# witch-phase2a.net
KiCad netlist of a schematic drawn in EAGLE
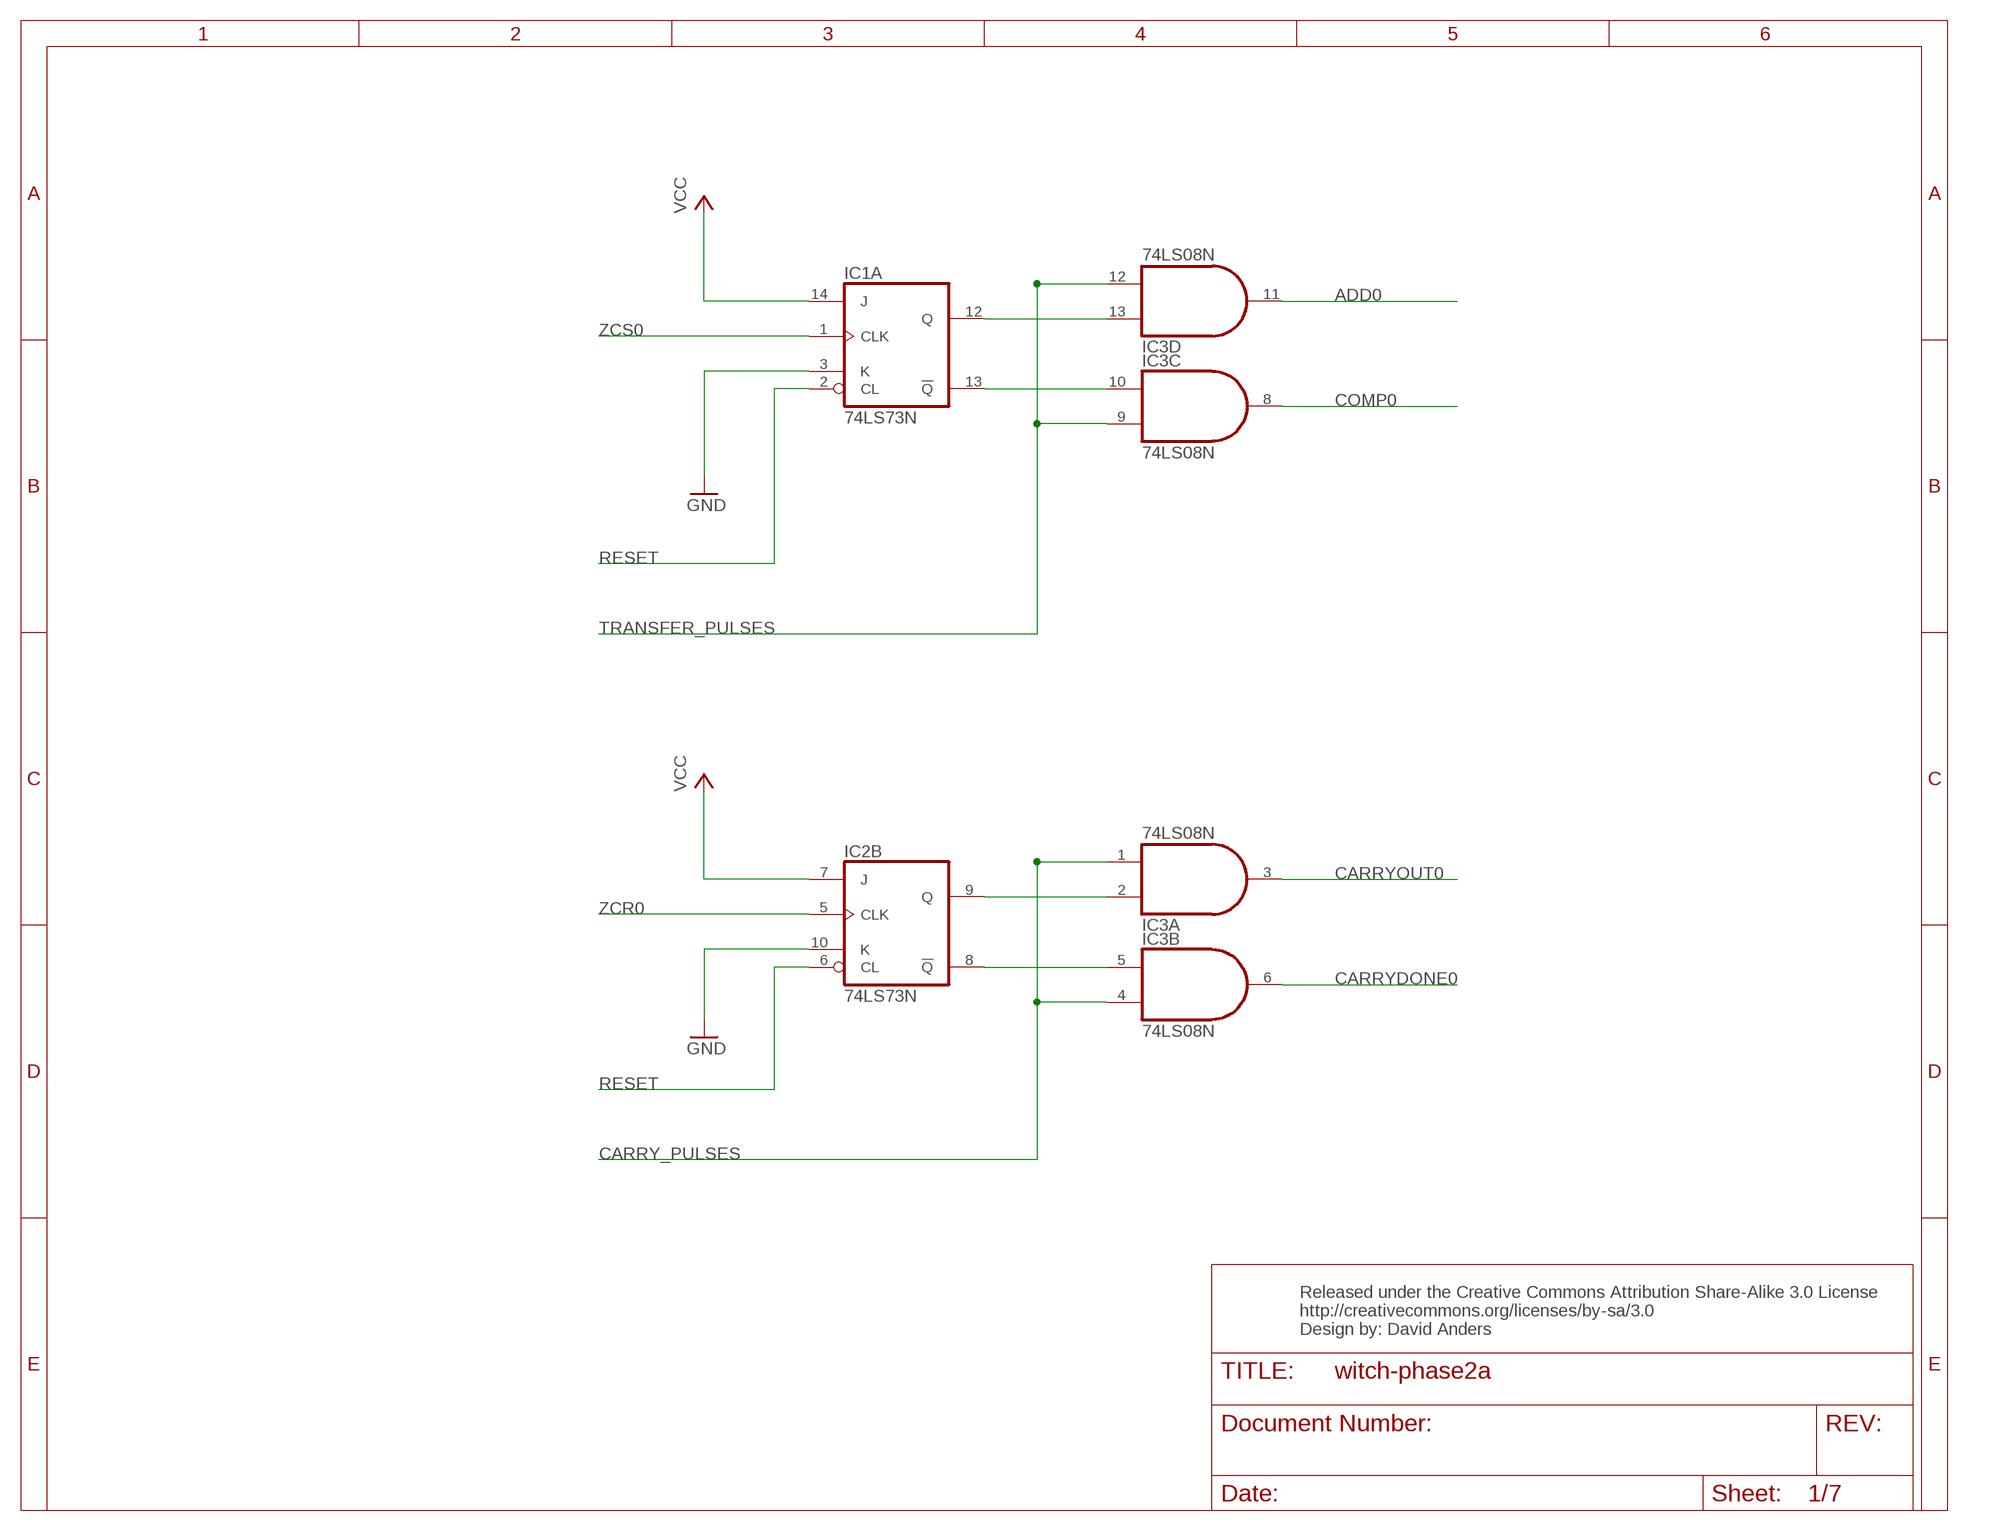
[diagram p0: schematic, sheet 1]
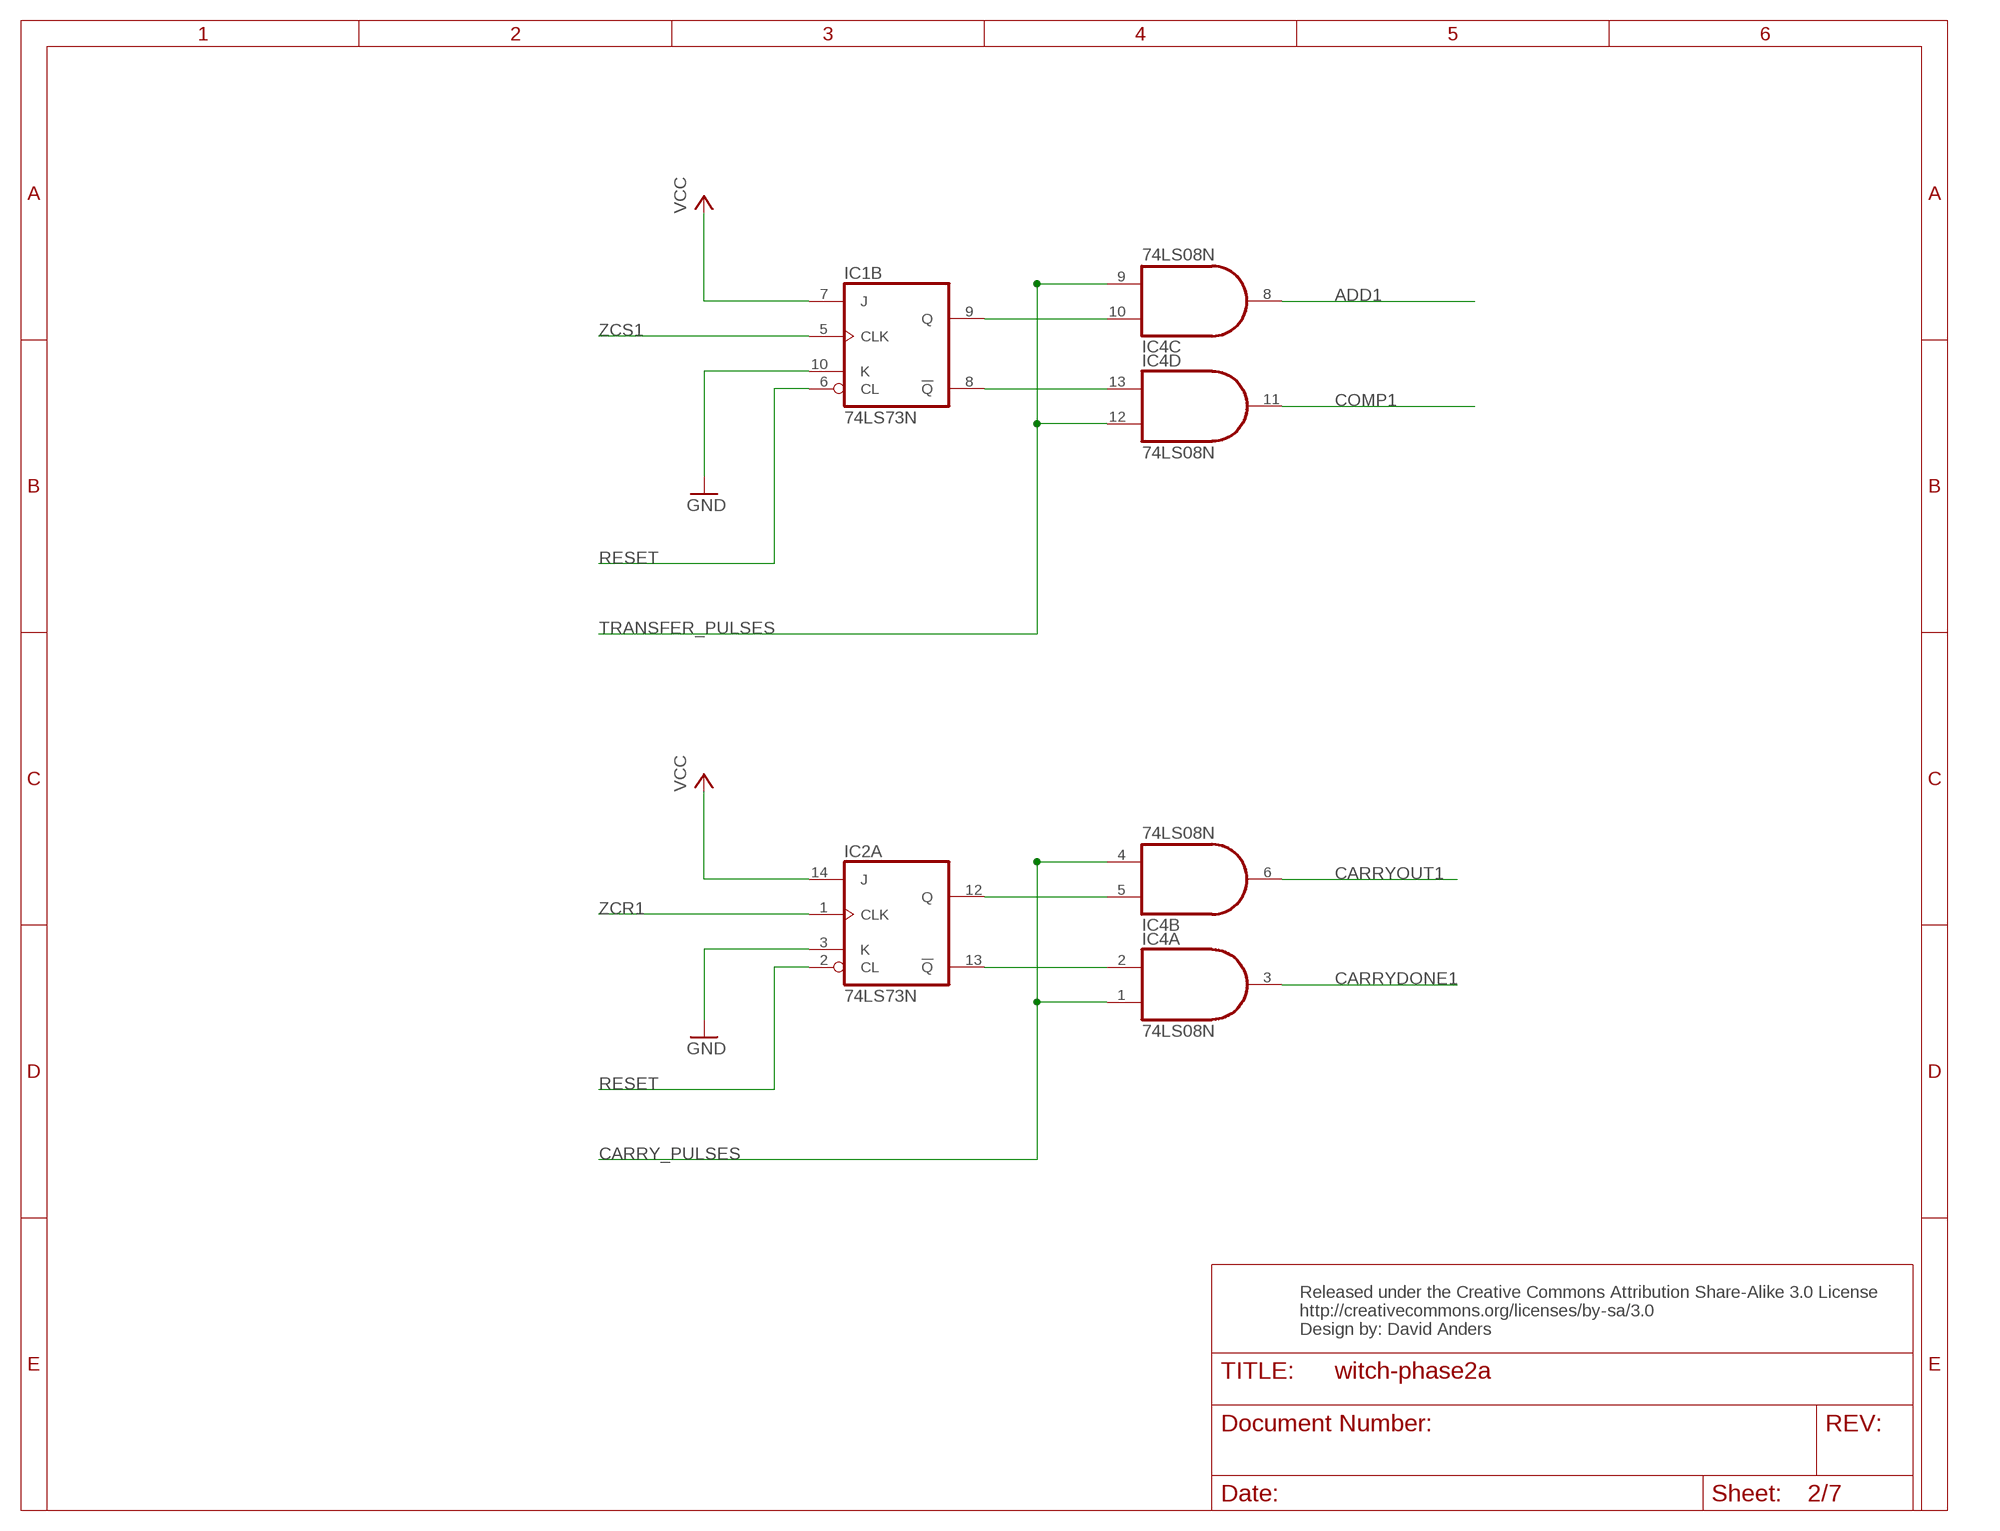
[diagram p1: schematic, sheet 2]
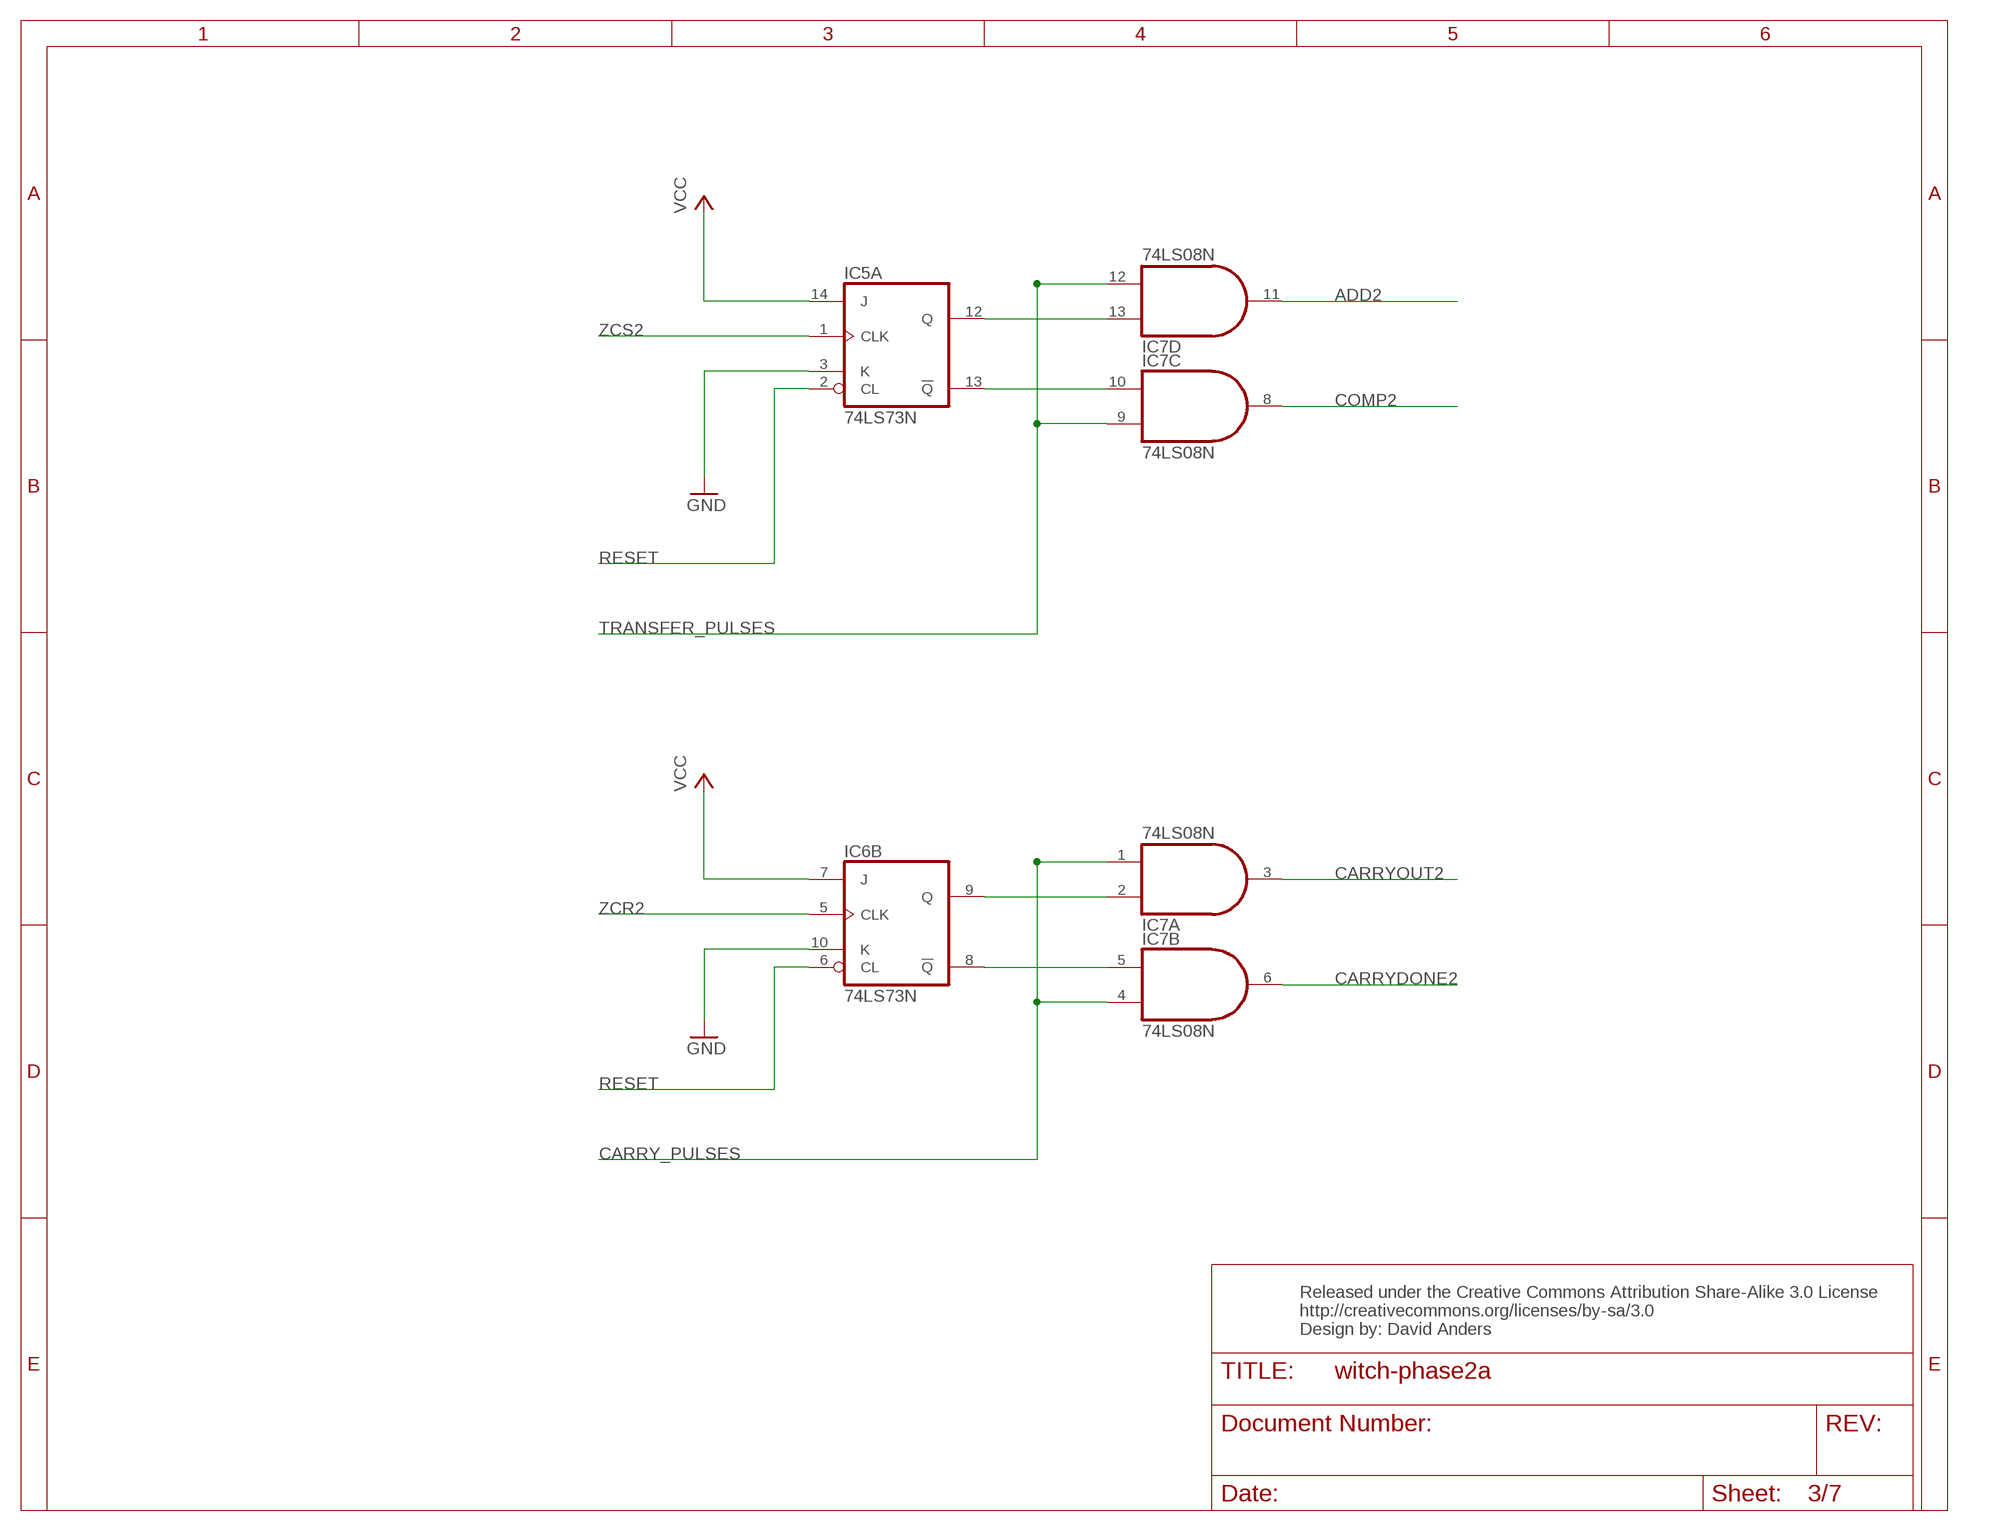
[diagram p2: schematic, sheet 3]
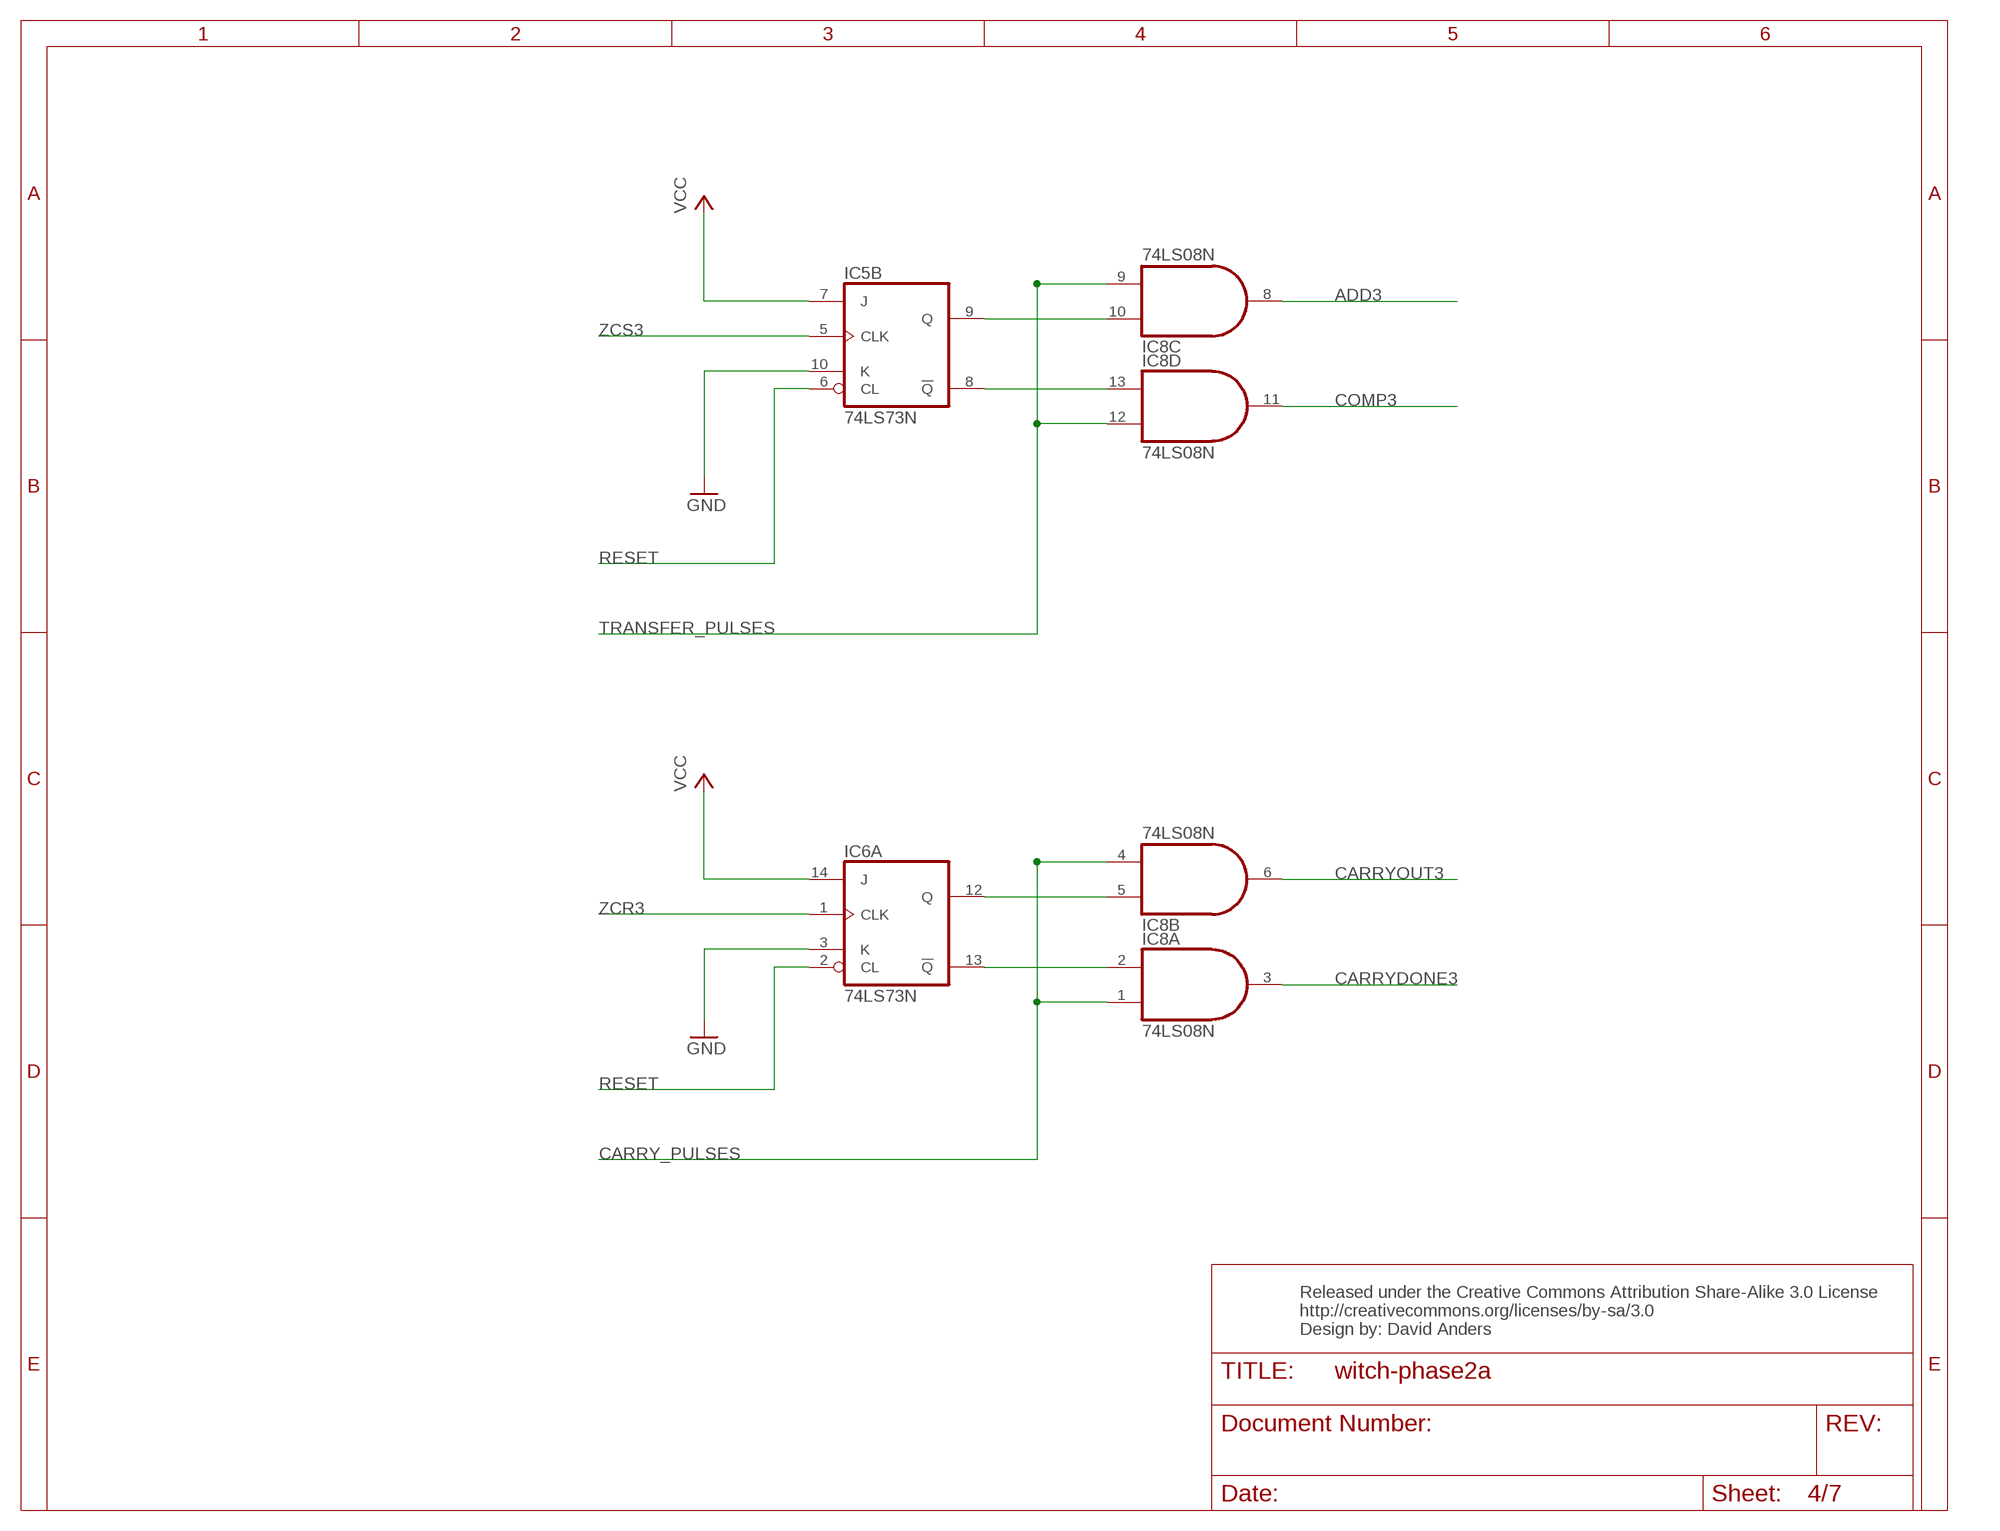
[diagram p3: schematic, sheet 4]
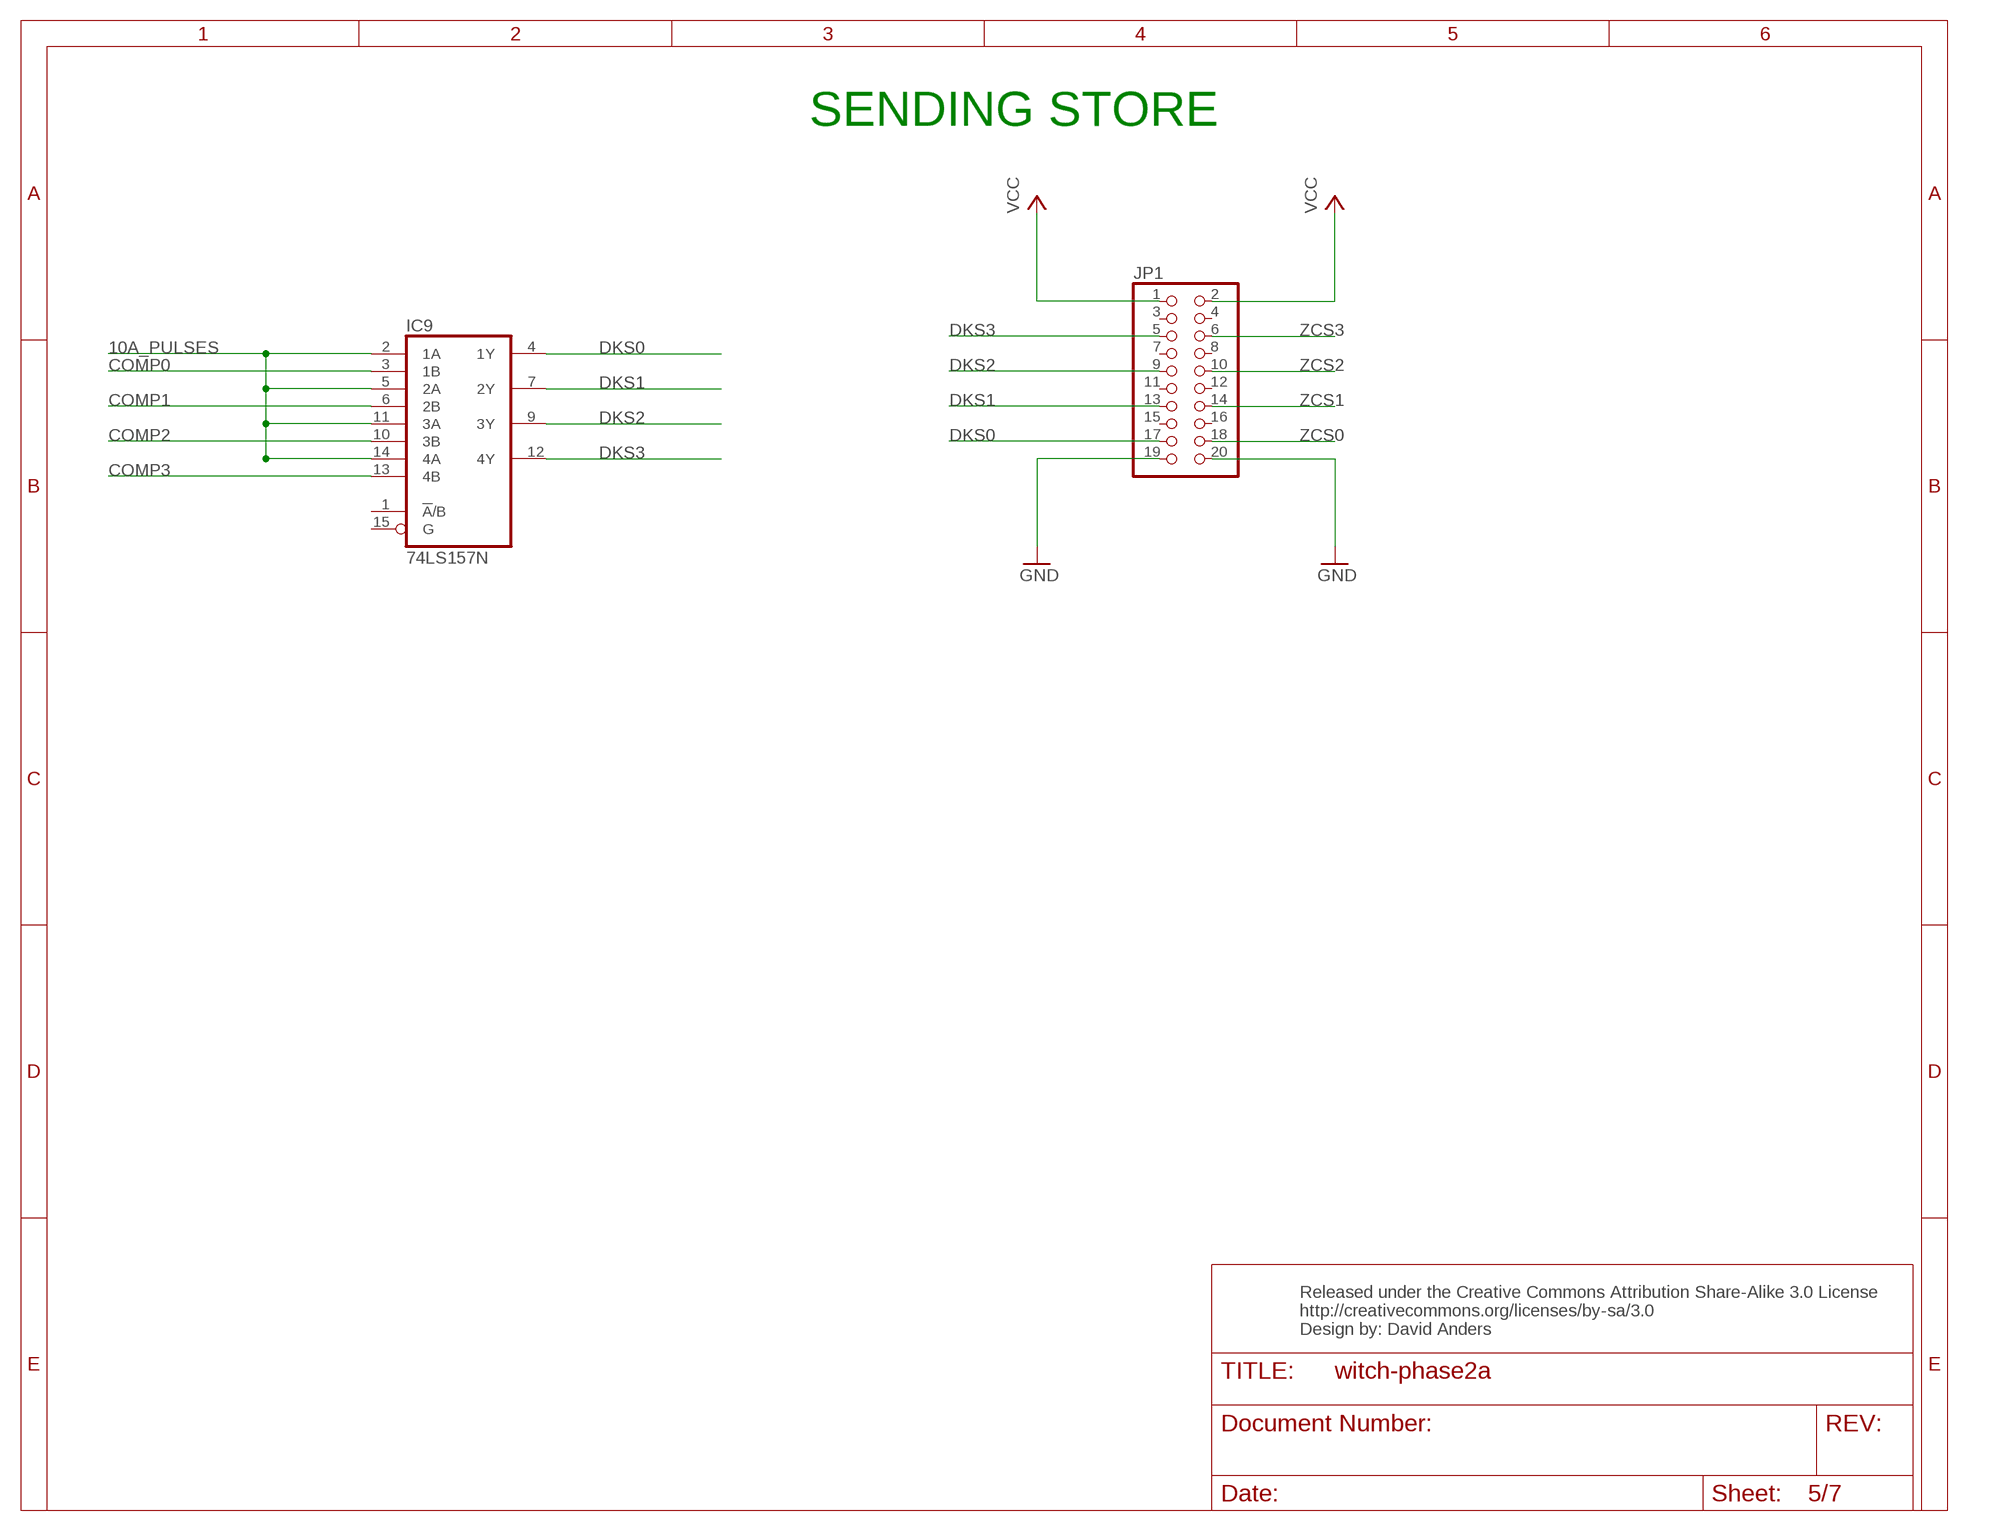
[diagram p4: schematic, sheet 5]
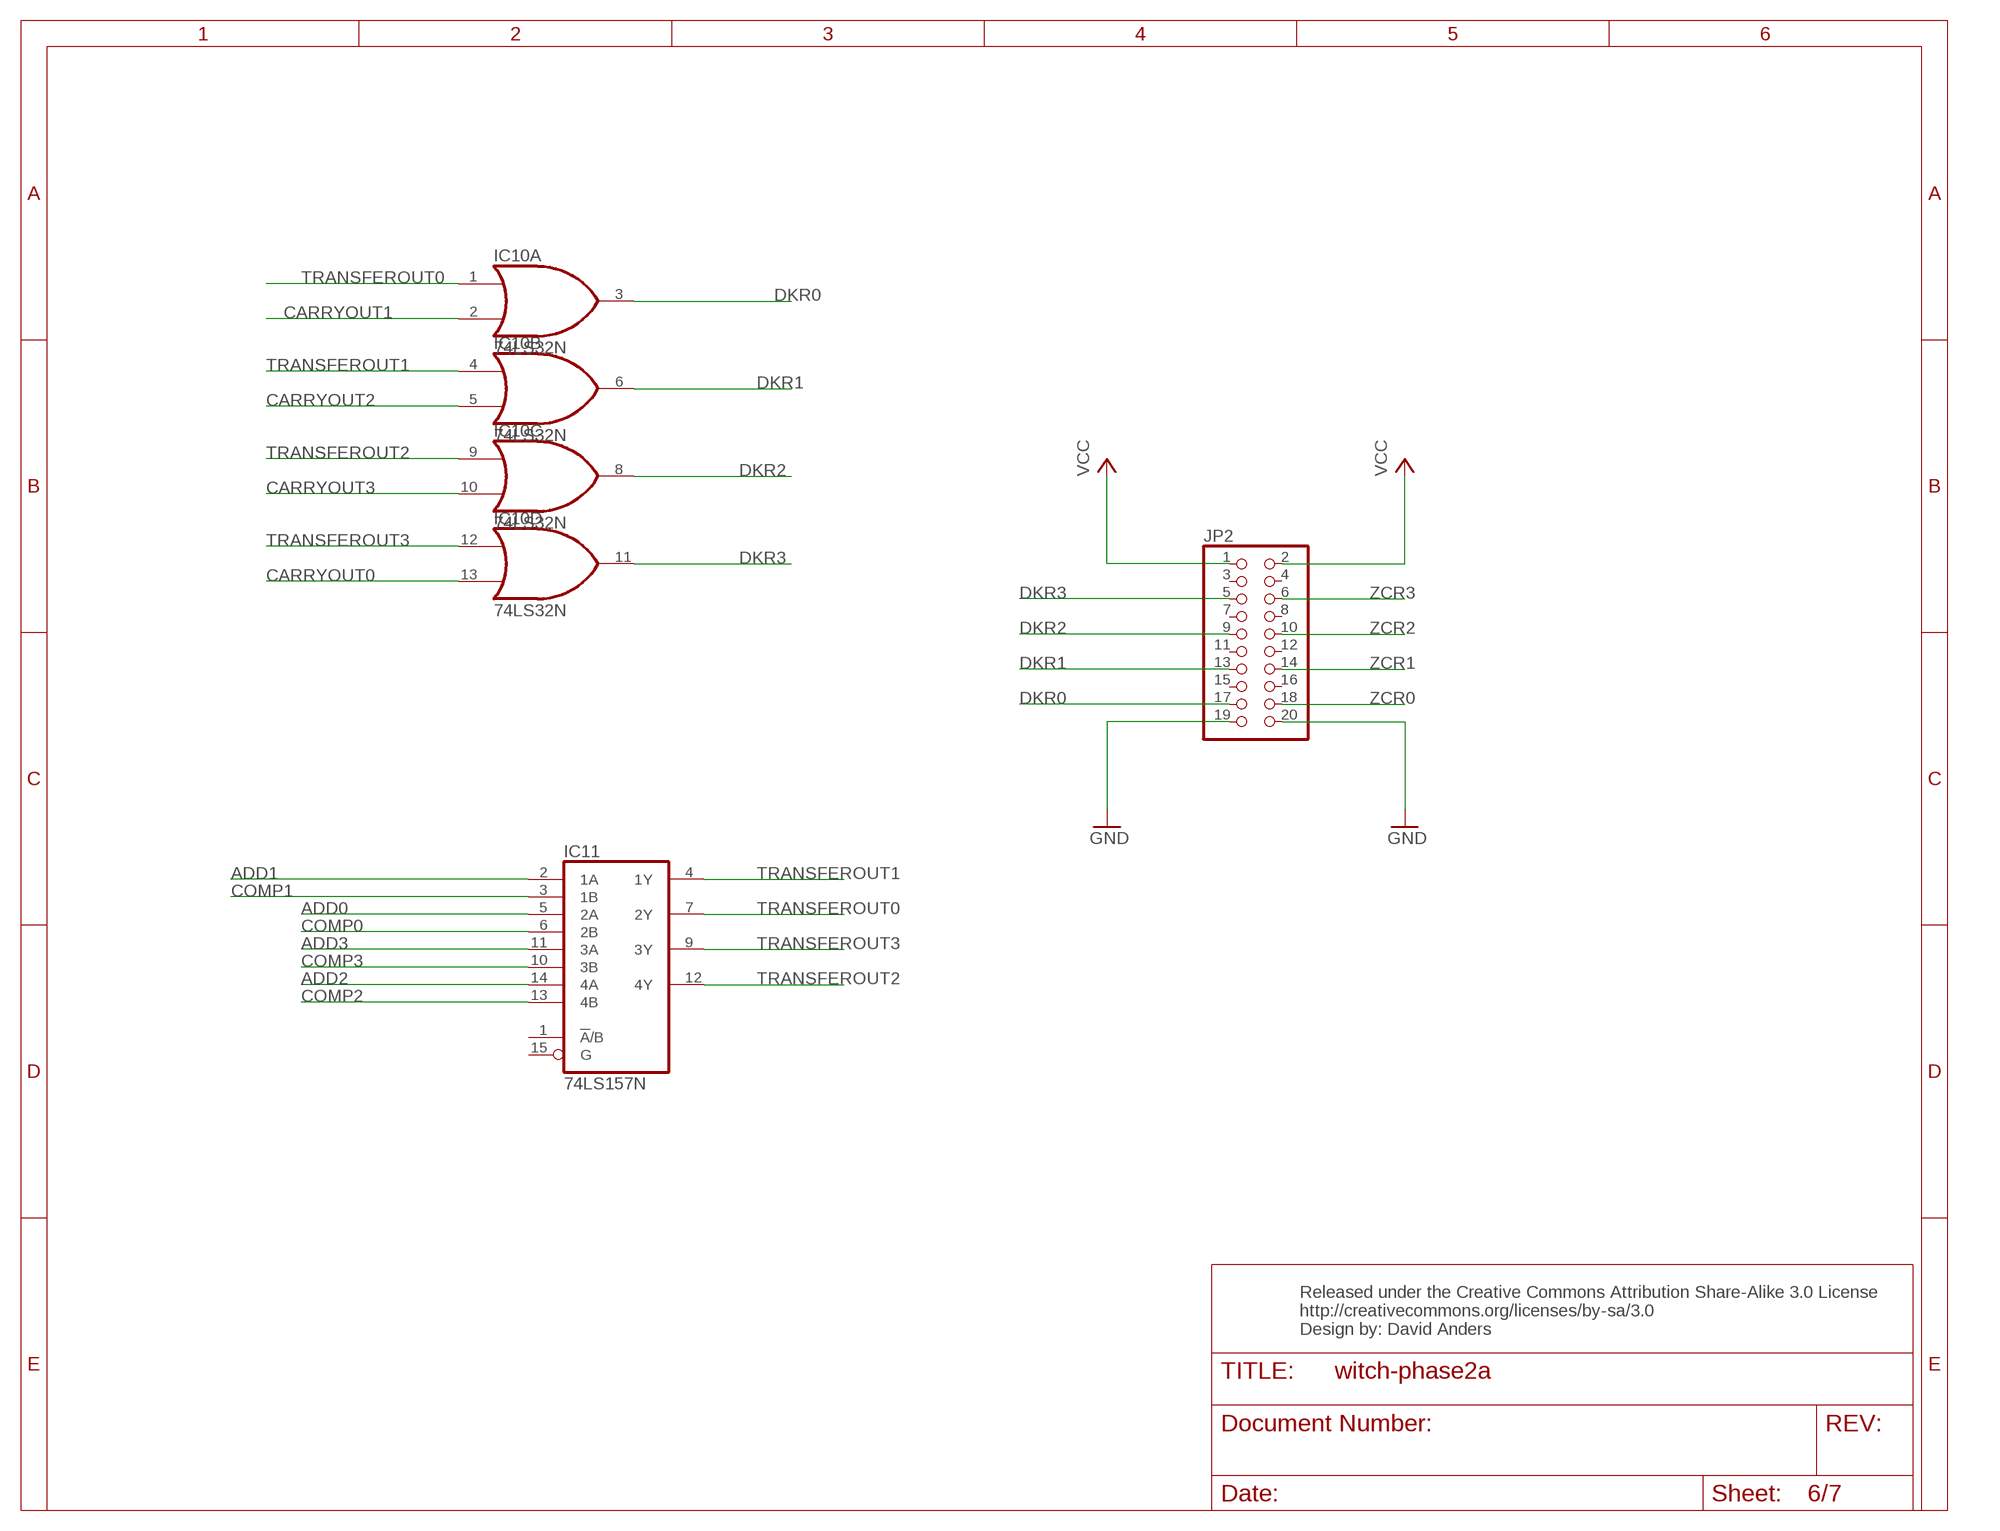
[diagram p5: schematic, sheet 6]
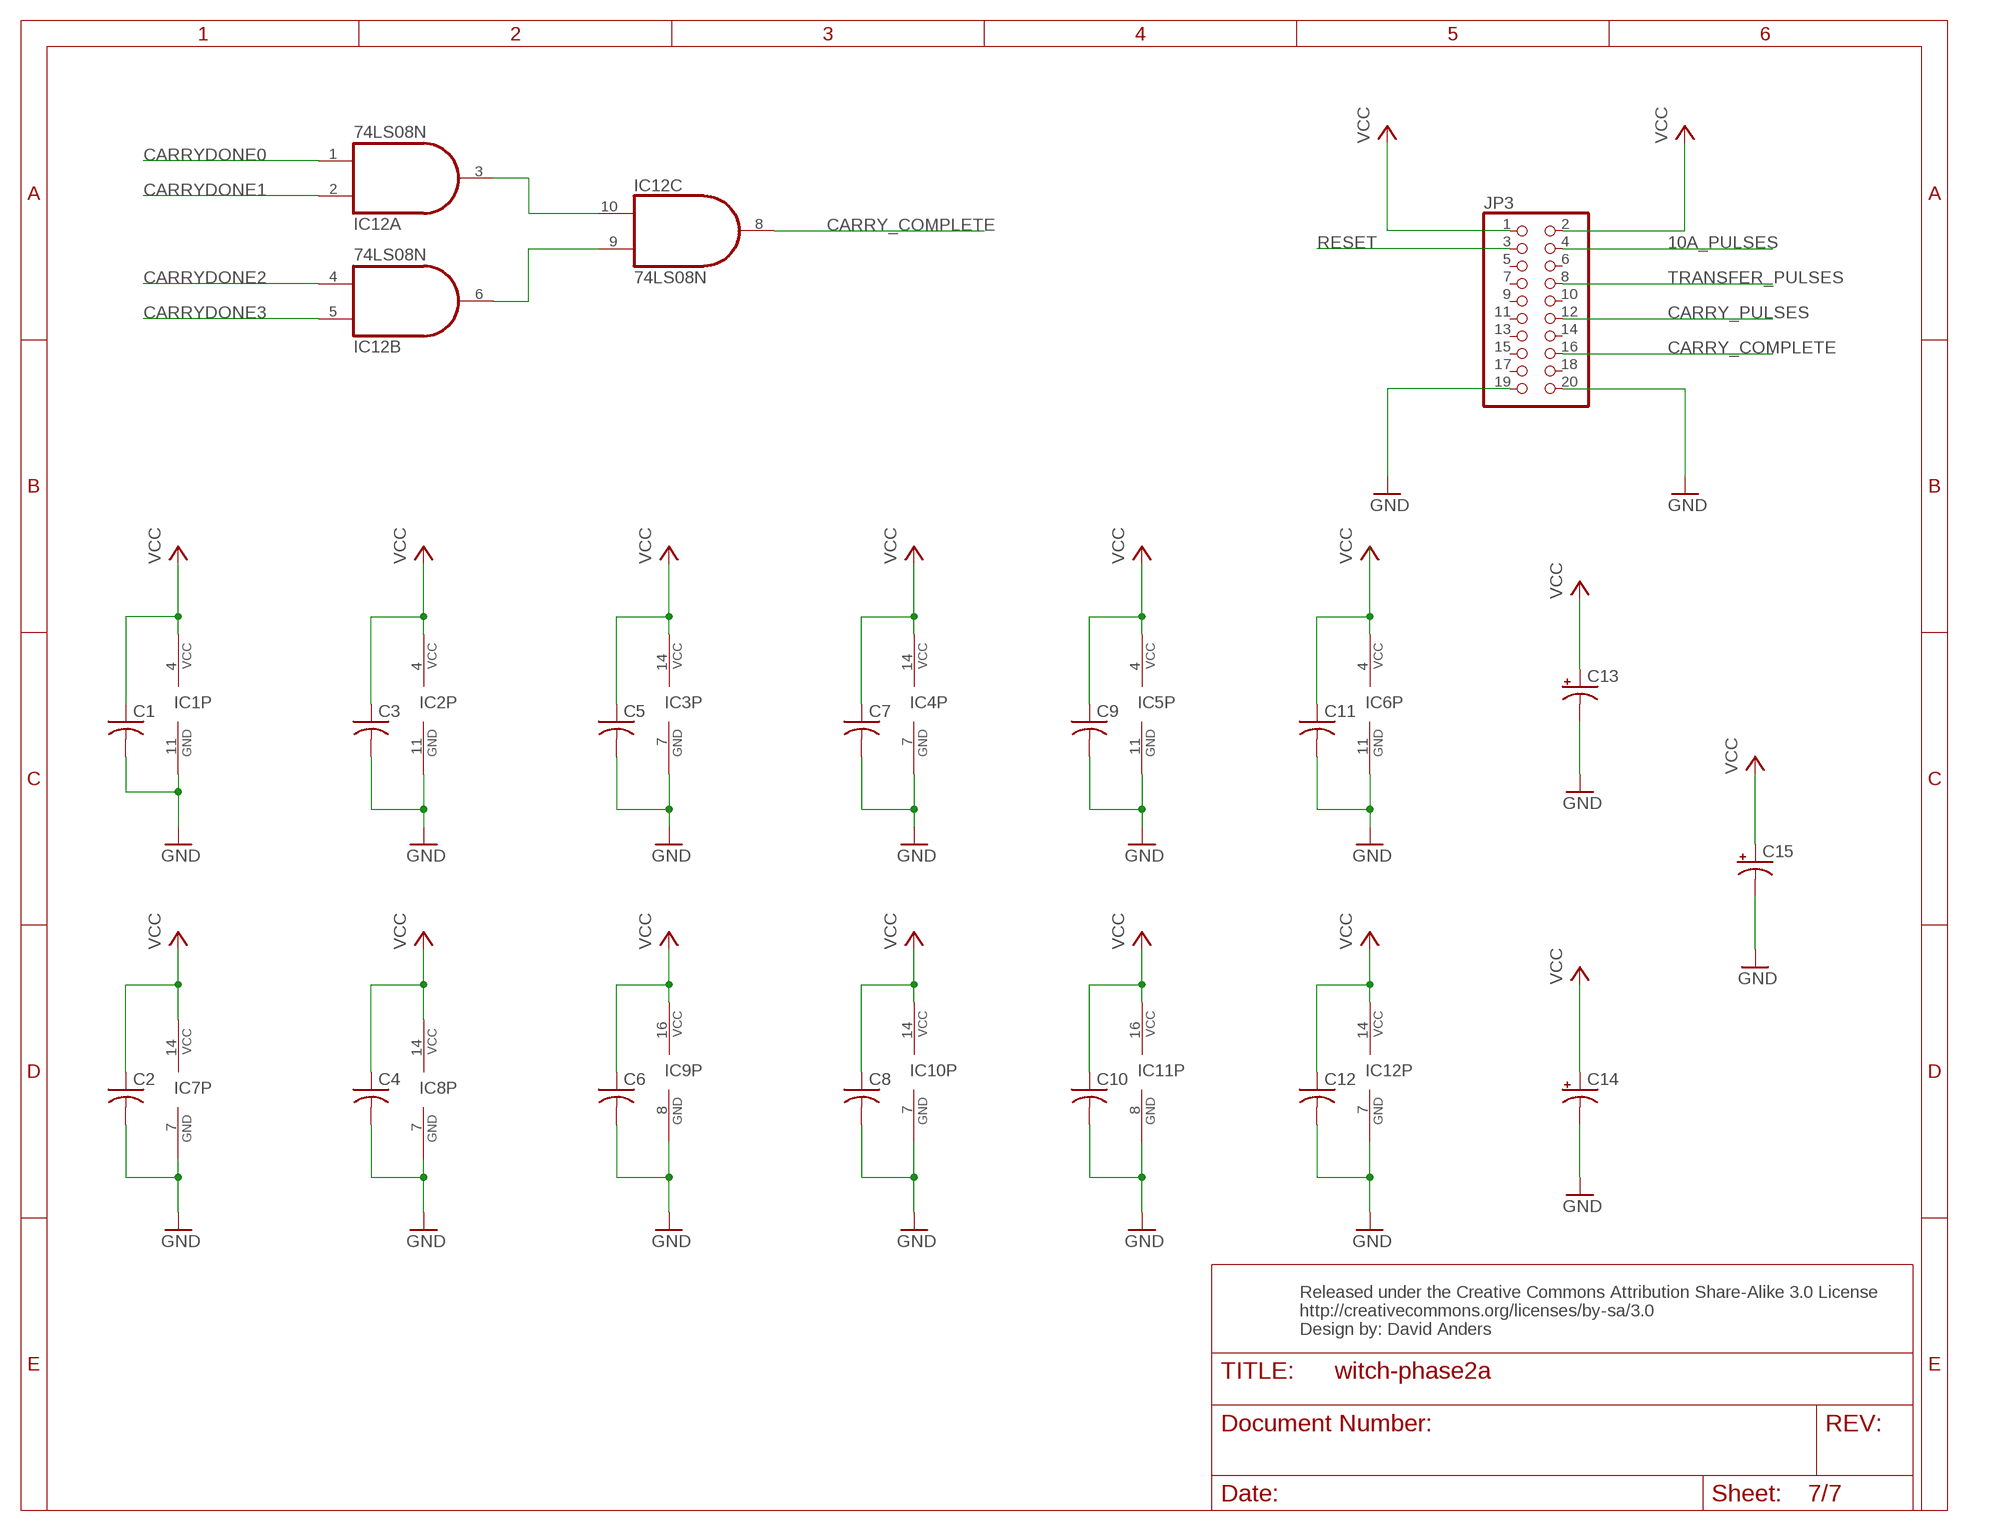
[diagram p6: schematic, sheet 7]

(export (version "E")
  (design (tool "Eeschema 10.0.6"))
  (components
    (comp (ref "IC9")
      (value "74LS157N")
      (footprint "eagle-import:DIL16")
      (libsource (lib "eagle-import") (part "74157NLS"))
    )
    (comp (ref "JP1")
      (value "PINHD-2X10")
      (footprint "eagle-import:2X10")
      (libsource (lib "eagle-import") (part "PINHD-2X10"))
    )
    (comp (ref "IC10")
      (value "74LS32N")
      (footprint "eagle-import:DIL14")
      (libsource (lib "eagle-import") (part "7432NLS"))
    )
    (comp (ref "IC11")
      (value "74LS157N")
      (footprint "eagle-import:DIL16")
      (libsource (lib "eagle-import") (part "74157NLS"))
    )
    (comp (ref "JP2")
      (value "PINHD-2X10")
      (footprint "eagle-import:2X10")
      (libsource (lib "eagle-import") (part "PINHD-2X10"))
    )
    (comp (ref "C1")
      (value "C-US025-025X050")
      (footprint "eagle-import:C025-025X050")
      (libsource (lib "eagle-import") (part "C-US025-025X050"))
    )
    (comp (ref "C2")
      (value "C-US025-025X050")
      (footprint "eagle-import:C025-025X050")
      (libsource (lib "eagle-import") (part "C-US025-025X050"))
    )
    (comp (ref "C3")
      (value "C-US025-025X050")
      (footprint "eagle-import:C025-025X050")
      (libsource (lib "eagle-import") (part "C-US025-025X050"))
    )
    (comp (ref "C4")
      (value "C-US025-025X050")
      (footprint "eagle-import:C025-025X050")
      (libsource (lib "eagle-import") (part "C-US025-025X050"))
    )
    (comp (ref "C5")
      (value "C-US025-025X050")
      (footprint "eagle-import:C025-025X050")
      (libsource (lib "eagle-import") (part "C-US025-025X050"))
    )
    (comp (ref "C6")
      (value "C-US025-025X050")
      (footprint "eagle-import:C025-025X050")
      (libsource (lib "eagle-import") (part "C-US025-025X050"))
    )
    (comp (ref "C7")
      (value "C-US025-025X050")
      (footprint "eagle-import:C025-025X050")
      (libsource (lib "eagle-import") (part "C-US025-025X050"))
    )
    (comp (ref "C8")
      (value "C-US025-025X050")
      (footprint "eagle-import:C025-025X050")
      (libsource (lib "eagle-import") (part "C-US025-025X050"))
    )
    (comp (ref "C9")
      (value "C-US025-025X050")
      (footprint "eagle-import:C025-025X050")
      (libsource (lib "eagle-import") (part "C-US025-025X050"))
    )
    (comp (ref "C10")
      (value "C-US025-025X050")
      (footprint "eagle-import:C025-025X050")
      (libsource (lib "eagle-import") (part "C-US025-025X050"))
    )
    (comp (ref "C11")
      (value "C-US025-025X050")
      (footprint "eagle-import:C025-025X050")
      (libsource (lib "eagle-import") (part "C-US025-025X050"))
    )
    (comp (ref "C12")
      (value "C-US025-025X050")
      (footprint "eagle-import:C025-025X050")
      (libsource (lib "eagle-import") (part "C-US025-025X050"))
    )
    (comp (ref "C13")
      (value "CPOL-USE2-5")
      (footprint "eagle-import:E2-5")
      (libsource (lib "eagle-import") (part "CPOL-USE2-5"))
    )
    (comp (ref "C14")
      (value "CPOL-USE2-5")
      (footprint "eagle-import:E2-5")
      (libsource (lib "eagle-import") (part "CPOL-USE2-5"))
    )
    (comp (ref "C15")
      (value "CPOL-USE2-5")
      (footprint "eagle-import:E2-5")
      (libsource (lib "eagle-import") (part "CPOL-USE2-5"))
    )
    (comp (ref "IC1")
      (value "74LS73N")
      (footprint "eagle-import:DIL14")
      (libsource (lib "eagle-import") (part "7473NLS"))
    )
    (comp (ref "IC2")
      (value "74LS73N")
      (footprint "eagle-import:DIL14")
      (libsource (lib "eagle-import") (part "7473NLS"))
    )
    (comp (ref "IC3")
      (value "74LS08N")
      (footprint "eagle-import:DIL14")
      (libsource (lib "eagle-import") (part "7408NLS"))
    )
    (comp (ref "IC4")
      (value "74LS08N")
      (footprint "eagle-import:DIL14")
      (libsource (lib "eagle-import") (part "7408NLS"))
    )
    (comp (ref "IC5")
      (value "74LS73N")
      (footprint "eagle-import:DIL14")
      (libsource (lib "eagle-import") (part "7473NLS"))
    )
    (comp (ref "IC6")
      (value "74LS73N")
      (footprint "eagle-import:DIL14")
      (libsource (lib "eagle-import") (part "7473NLS"))
    )
    (comp (ref "IC7")
      (value "74LS08N")
      (footprint "eagle-import:DIL14")
      (libsource (lib "eagle-import") (part "7408NLS"))
    )
    (comp (ref "IC8")
      (value "74LS08N")
      (footprint "eagle-import:DIL14")
      (libsource (lib "eagle-import") (part "7408NLS"))
    )
    (comp (ref "IC12")
      (value "74LS08N")
      (footprint "eagle-import:DIL14")
      (libsource (lib "eagle-import") (part "7408NLS"))
    )
    (comp (ref "JP3")
      (value "PINHD-2X10")
      (footprint "eagle-import:2X10")
      (libsource (lib "eagle-import") (part "PINHD-2X10"))
    )
  )
  (nets
    (net (code "1") (name "10A_PULSES") (class "Default")
      (node (ref "IC9") (pin "11") (pinfunction "3A_11") (pintype "input"))
      (node (ref "IC9") (pin "14") (pinfunction "4A_14") (pintype "input"))
      (node (ref "IC9") (pin "2") (pinfunction "1A_2") (pintype "input"))
      (node (ref "IC9") (pin "5") (pinfunction "2A_5") (pintype "input"))
      (node (ref "JP3") (pin "4") (pinfunction "4_4") (pintype "passive"))
    )
    (net (code "2") (name "ADD0") (class "Default")
      (node (ref "IC11") (pin "5") (pinfunction "2A_5") (pintype "input"))
      (node (ref "IC3") (pin "11") (pinfunction "O_11") (pintype "output"))
    )
    (net (code "3") (name "ADD1") (class "Default")
      (node (ref "IC11") (pin "2") (pinfunction "1A_2") (pintype "input"))
      (node (ref "IC4") (pin "8") (pinfunction "O_8") (pintype "output"))
    )
    (net (code "4") (name "ADD2") (class "Default")
      (node (ref "IC11") (pin "14") (pinfunction "4A_14") (pintype "input"))
      (node (ref "IC7") (pin "11") (pinfunction "O_11") (pintype "output"))
    )
    (net (code "5") (name "ADD3") (class "Default")
      (node (ref "IC11") (pin "11") (pinfunction "3A_11") (pintype "input"))
      (node (ref "IC8") (pin "8") (pinfunction "O_8") (pintype "output"))
    )
    (net (code "6") (name "CARRYDONE0") (class "Default")
      (node (ref "IC12") (pin "1") (pinfunction "I0_1") (pintype "input"))
      (node (ref "IC3") (pin "6") (pinfunction "O_6") (pintype "output"))
    )
    (net (code "7") (name "CARRYDONE1") (class "Default")
      (node (ref "IC12") (pin "2") (pinfunction "I1_2") (pintype "input"))
      (node (ref "IC4") (pin "3") (pinfunction "O_3") (pintype "output"))
    )
    (net (code "8") (name "CARRYDONE2") (class "Default")
      (node (ref "IC12") (pin "4") (pinfunction "I0_4") (pintype "input"))
      (node (ref "IC7") (pin "6") (pinfunction "O_6") (pintype "output"))
    )
    (net (code "9") (name "CARRYDONE3") (class "Default")
      (node (ref "IC12") (pin "5") (pinfunction "I1_5") (pintype "input"))
      (node (ref "IC8") (pin "3") (pinfunction "O_3") (pintype "output"))
    )
    (net (code "10") (name "CARRYOUT0") (class "Default")
      (node (ref "IC10") (pin "13") (pinfunction "I1_13") (pintype "input"))
      (node (ref "IC3") (pin "3") (pinfunction "O_3") (pintype "output"))
    )
    (net (code "11") (name "CARRYOUT1") (class "Default")
      (node (ref "IC10") (pin "2") (pinfunction "I1_2") (pintype "input"))
      (node (ref "IC4") (pin "6") (pinfunction "O_6") (pintype "output"))
    )
    (net (code "12") (name "CARRYOUT2") (class "Default")
      (node (ref "IC10") (pin "5") (pinfunction "I1_5") (pintype "input"))
      (node (ref "IC7") (pin "3") (pinfunction "O_3") (pintype "output"))
    )
    (net (code "13") (name "CARRYOUT3") (class "Default")
      (node (ref "IC10") (pin "10") (pinfunction "I1_10") (pintype "input"))
      (node (ref "IC8") (pin "6") (pinfunction "O_6") (pintype "output"))
    )
    (net (code "14") (name "CARRY_COMPLETE") (class "Default")
      (node (ref "IC12") (pin "8") (pinfunction "O_8") (pintype "output"))
      (node (ref "JP3") (pin "16") (pinfunction "16_16") (pintype "passive"))
    )
    (net (code "15") (name "CARRY_PULSES") (class "Default")
      (node (ref "IC3") (pin "1") (pinfunction "I0_1") (pintype "input"))
      (node (ref "IC3") (pin "4") (pinfunction "I0_4") (pintype "input"))
      (node (ref "IC4") (pin "1") (pinfunction "I0_1") (pintype "input"))
      (node (ref "IC4") (pin "4") (pinfunction "I0_4") (pintype "input"))
      (node (ref "IC7") (pin "1") (pinfunction "I0_1") (pintype "input"))
      (node (ref "IC7") (pin "4") (pinfunction "I0_4") (pintype "input"))
      (node (ref "IC8") (pin "1") (pinfunction "I0_1") (pintype "input"))
      (node (ref "IC8") (pin "4") (pinfunction "I0_4") (pintype "input"))
      (node (ref "JP3") (pin "12") (pinfunction "12_12") (pintype "passive"))
    )
    (net (code "16") (name "COMP0") (class "Default")
      (node (ref "IC11") (pin "6") (pinfunction "2B_6") (pintype "input"))
      (node (ref "IC3") (pin "8") (pinfunction "O_8") (pintype "output"))
      (node (ref "IC9") (pin "3") (pinfunction "1B_3") (pintype "input"))
    )
    (net (code "17") (name "COMP1") (class "Default")
      (node (ref "IC11") (pin "3") (pinfunction "1B_3") (pintype "input"))
      (node (ref "IC4") (pin "11") (pinfunction "O_11") (pintype "output"))
      (node (ref "IC9") (pin "6") (pinfunction "2B_6") (pintype "input"))
    )
    (net (code "18") (name "COMP2") (class "Default")
      (node (ref "IC11") (pin "13") (pinfunction "4B_13") (pintype "input"))
      (node (ref "IC7") (pin "8") (pinfunction "O_8") (pintype "output"))
      (node (ref "IC9") (pin "10") (pinfunction "3B_10") (pintype "input"))
    )
    (net (code "19") (name "COMP3") (class "Default")
      (node (ref "IC11") (pin "10") (pinfunction "3B_10") (pintype "input"))
      (node (ref "IC8") (pin "11") (pinfunction "O_11") (pintype "output"))
      (node (ref "IC9") (pin "13") (pinfunction "4B_13") (pintype "input"))
    )
    (net (code "20") (name "DKR0") (class "Default")
      (node (ref "IC10") (pin "3") (pinfunction "O_3") (pintype "output"))
      (node (ref "JP2") (pin "17") (pinfunction "17_17") (pintype "passive"))
    )
    (net (code "21") (name "DKR1") (class "Default")
      (node (ref "IC10") (pin "6") (pinfunction "O_6") (pintype "output"))
      (node (ref "JP2") (pin "13") (pinfunction "13_13") (pintype "passive"))
    )
    (net (code "22") (name "DKR2") (class "Default")
      (node (ref "IC10") (pin "8") (pinfunction "O_8") (pintype "output"))
      (node (ref "JP2") (pin "9") (pinfunction "9_9") (pintype "passive"))
    )
    (net (code "23") (name "DKR3") (class "Default")
      (node (ref "IC10") (pin "11") (pinfunction "O_11") (pintype "output"))
      (node (ref "JP2") (pin "5") (pinfunction "5_5") (pintype "passive"))
    )
    (net (code "24") (name "DKS0") (class "Default")
      (node (ref "IC9") (pin "4") (pinfunction "1Y_4") (pintype "output"))
      (node (ref "JP1") (pin "17") (pinfunction "17_17") (pintype "passive"))
    )
    (net (code "25") (name "DKS1") (class "Default")
      (node (ref "IC9") (pin "7") (pinfunction "2Y_7") (pintype "output"))
      (node (ref "JP1") (pin "13") (pinfunction "13_13") (pintype "passive"))
    )
    (net (code "26") (name "DKS2") (class "Default")
      (node (ref "IC9") (pin "9") (pinfunction "3Y_9") (pintype "output"))
      (node (ref "JP1") (pin "9") (pinfunction "9_9") (pintype "passive"))
    )
    (net (code "27") (name "DKS3") (class "Default")
      (node (ref "IC9") (pin "12") (pinfunction "4Y_12") (pintype "output"))
      (node (ref "JP1") (pin "5") (pinfunction "5_5") (pintype "passive"))
    )
    (net (code "28") (name "GND") (class "Default")
      (node (ref "C1") (pin "2") (pinfunction "2_2") (pintype "passive"))
      (node (ref "C10") (pin "2") (pinfunction "2_2") (pintype "passive"))
      (node (ref "C11") (pin "2") (pinfunction "2_2") (pintype "passive"))
      (node (ref "C12") (pin "2") (pinfunction "2_2") (pintype "passive"))
      (node (ref "C13") (pin "-") (pinfunction "-_-") (pintype "passive"))
      (node (ref "C14") (pin "-") (pinfunction "-_-") (pintype "passive"))
      (node (ref "C15") (pin "-") (pinfunction "-_-") (pintype "passive"))
      (node (ref "C2") (pin "2") (pinfunction "2_2") (pintype "passive"))
      (node (ref "C3") (pin "2") (pinfunction "2_2") (pintype "passive"))
      (node (ref "C4") (pin "2") (pinfunction "2_2") (pintype "passive"))
      (node (ref "C5") (pin "2") (pinfunction "2_2") (pintype "passive"))
      (node (ref "C6") (pin "2") (pinfunction "2_2") (pintype "passive"))
      (node (ref "C7") (pin "2") (pinfunction "2_2") (pintype "passive"))
      (node (ref "C8") (pin "2") (pinfunction "2_2") (pintype "passive"))
      (node (ref "C9") (pin "2") (pinfunction "2_2") (pintype "passive"))
      (node (ref "IC1") (pin "10") (pinfunction "K_10") (pintype "input"))
      (node (ref "IC1") (pin "11") (pinfunction "GND_11") (pintype "power_in"))
      (node (ref "IC1") (pin "3") (pinfunction "K_3") (pintype "input"))
      (node (ref "IC10") (pin "7") (pinfunction "GND_7") (pintype "power_in"))
      (node (ref "IC11") (pin "8") (pinfunction "GND_8") (pintype "power_in"))
      (node (ref "IC12") (pin "7") (pinfunction "GND_7") (pintype "power_in"))
      (node (ref "IC2") (pin "10") (pinfunction "K_10") (pintype "input"))
      (node (ref "IC2") (pin "11") (pinfunction "GND_11") (pintype "power_in"))
      (node (ref "IC2") (pin "3") (pinfunction "K_3") (pintype "input"))
      (node (ref "IC3") (pin "7") (pinfunction "GND_7") (pintype "power_in"))
      (node (ref "IC4") (pin "7") (pinfunction "GND_7") (pintype "power_in"))
      (node (ref "IC5") (pin "10") (pinfunction "K_10") (pintype "input"))
      (node (ref "IC5") (pin "11") (pinfunction "GND_11") (pintype "power_in"))
      (node (ref "IC5") (pin "3") (pinfunction "K_3") (pintype "input"))
      (node (ref "IC6") (pin "10") (pinfunction "K_10") (pintype "input"))
      (node (ref "IC6") (pin "11") (pinfunction "GND_11") (pintype "power_in"))
      (node (ref "IC6") (pin "3") (pinfunction "K_3") (pintype "input"))
      (node (ref "IC7") (pin "7") (pinfunction "GND_7") (pintype "power_in"))
      (node (ref "IC8") (pin "7") (pinfunction "GND_7") (pintype "power_in"))
      (node (ref "IC9") (pin "8") (pinfunction "GND_8") (pintype "power_in"))
      (node (ref "JP1") (pin "19") (pinfunction "19_19") (pintype "passive"))
      (node (ref "JP1") (pin "20") (pinfunction "20_20") (pintype "passive"))
      (node (ref "JP2") (pin "19") (pinfunction "19_19") (pintype "passive"))
      (node (ref "JP2") (pin "20") (pinfunction "20_20") (pintype "passive"))
      (node (ref "JP3") (pin "19") (pinfunction "19_19") (pintype "passive"))
      (node (ref "JP3") (pin "20") (pinfunction "20_20") (pintype "passive"))
    )
    (net (code "29") (name "Net-(IC1A-Q)") (class "Default")
      (node (ref "IC1") (pin "12") (pinfunction "Q_12") (pintype "output"))
      (node (ref "IC3") (pin "13") (pinfunction "I1_13") (pintype "input"))
    )
    (net (code "30") (name "Net-(IC1A-~{Q})") (class "Default")
      (node (ref "IC1") (pin "13") (pinfunction "~{Q}_13") (pintype "output"))
      (node (ref "IC3") (pin "10") (pinfunction "I1_10") (pintype "input"))
    )
    (net (code "31") (name "Net-(IC1B-Q)") (class "Default")
      (node (ref "IC1") (pin "9") (pinfunction "Q_9") (pintype "output"))
      (node (ref "IC4") (pin "10") (pinfunction "I1_10") (pintype "input"))
    )
    (net (code "32") (name "Net-(IC1B-~{Q})") (class "Default")
      (node (ref "IC1") (pin "8") (pinfunction "~{Q}_8") (pintype "output"))
      (node (ref "IC4") (pin "13") (pinfunction "I1_13") (pintype "input"))
    )
    (net (code "33") (name "Net-(IC2A-Q)") (class "Default")
      (node (ref "IC2") (pin "12") (pinfunction "Q_12") (pintype "output"))
      (node (ref "IC4") (pin "5") (pinfunction "I1_5") (pintype "input"))
    )
    (net (code "34") (name "Net-(IC2A-~{Q})") (class "Default")
      (node (ref "IC2") (pin "13") (pinfunction "~{Q}_13") (pintype "output"))
      (node (ref "IC4") (pin "2") (pinfunction "I1_2") (pintype "input"))
    )
    (net (code "35") (name "Net-(IC2B-Q)") (class "Default")
      (node (ref "IC2") (pin "9") (pinfunction "Q_9") (pintype "output"))
      (node (ref "IC3") (pin "2") (pinfunction "I1_2") (pintype "input"))
    )
    (net (code "36") (name "Net-(IC2B-~{Q})") (class "Default")
      (node (ref "IC2") (pin "8") (pinfunction "~{Q}_8") (pintype "output"))
      (node (ref "IC3") (pin "5") (pinfunction "I1_5") (pintype "input"))
    )
    (net (code "37") (name "Net-(IC5A-Q)") (class "Default")
      (node (ref "IC5") (pin "12") (pinfunction "Q_12") (pintype "output"))
      (node (ref "IC7") (pin "13") (pinfunction "I1_13") (pintype "input"))
    )
    (net (code "38") (name "Net-(IC5A-~{Q})") (class "Default")
      (node (ref "IC5") (pin "13") (pinfunction "~{Q}_13") (pintype "output"))
      (node (ref "IC7") (pin "10") (pinfunction "I1_10") (pintype "input"))
    )
    (net (code "39") (name "Net-(IC5B-Q)") (class "Default")
      (node (ref "IC5") (pin "9") (pinfunction "Q_9") (pintype "output"))
      (node (ref "IC8") (pin "10") (pinfunction "I1_10") (pintype "input"))
    )
    (net (code "40") (name "Net-(IC5B-~{Q})") (class "Default")
      (node (ref "IC5") (pin "8") (pinfunction "~{Q}_8") (pintype "output"))
      (node (ref "IC8") (pin "13") (pinfunction "I1_13") (pintype "input"))
    )
    (net (code "41") (name "Net-(IC6A-Q)") (class "Default")
      (node (ref "IC6") (pin "12") (pinfunction "Q_12") (pintype "output"))
      (node (ref "IC8") (pin "5") (pinfunction "I1_5") (pintype "input"))
    )
    (net (code "42") (name "Net-(IC6A-~{Q})") (class "Default")
      (node (ref "IC6") (pin "13") (pinfunction "~{Q}_13") (pintype "output"))
      (node (ref "IC8") (pin "2") (pinfunction "I1_2") (pintype "input"))
    )
    (net (code "43") (name "Net-(IC6B-Q)") (class "Default")
      (node (ref "IC6") (pin "9") (pinfunction "Q_9") (pintype "output"))
      (node (ref "IC7") (pin "2") (pinfunction "I1_2") (pintype "input"))
    )
    (net (code "44") (name "Net-(IC6B-~{Q})") (class "Default")
      (node (ref "IC6") (pin "8") (pinfunction "~{Q}_8") (pintype "output"))
      (node (ref "IC7") (pin "5") (pinfunction "I1_5") (pintype "input"))
    )
    (net (code "45") (name "Net-(IC12A-O)") (class "Default")
      (node (ref "IC12") (pin "10") (pinfunction "I1_10") (pintype "input"))
      (node (ref "IC12") (pin "3") (pinfunction "O_3") (pintype "output"))
    )
    (net (code "46") (name "Net-(IC12B-O)") (class "Default")
      (node (ref "IC12") (pin "6") (pinfunction "O_6") (pintype "output"))
      (node (ref "IC12") (pin "9") (pinfunction "I0_9") (pintype "input"))
    )
    (net (code "47") (name "RESET") (class "Default")
      (node (ref "IC1") (pin "2") (pinfunction "CL_2") (pintype "input"))
      (node (ref "IC1") (pin "6") (pinfunction "CL_6") (pintype "input"))
      (node (ref "IC2") (pin "2") (pinfunction "CL_2") (pintype "input"))
      (node (ref "IC2") (pin "6") (pinfunction "CL_6") (pintype "input"))
      (node (ref "IC5") (pin "2") (pinfunction "CL_2") (pintype "input"))
      (node (ref "IC5") (pin "6") (pinfunction "CL_6") (pintype "input"))
      (node (ref "IC6") (pin "2") (pinfunction "CL_2") (pintype "input"))
      (node (ref "IC6") (pin "6") (pinfunction "CL_6") (pintype "input"))
      (node (ref "JP3") (pin "3") (pinfunction "3_3") (pintype "passive"))
    )
    (net (code "48") (name "TRANSFEROUT0") (class "Default")
      (node (ref "IC10") (pin "1") (pinfunction "I0_1") (pintype "input"))
      (node (ref "IC11") (pin "7") (pinfunction "2Y_7") (pintype "output"))
    )
    (net (code "49") (name "TRANSFEROUT1") (class "Default")
      (node (ref "IC10") (pin "4") (pinfunction "I0_4") (pintype "input"))
      (node (ref "IC11") (pin "4") (pinfunction "1Y_4") (pintype "output"))
    )
    (net (code "50") (name "TRANSFEROUT2") (class "Default")
      (node (ref "IC10") (pin "9") (pinfunction "I0_9") (pintype "input"))
      (node (ref "IC11") (pin "12") (pinfunction "4Y_12") (pintype "output"))
    )
    (net (code "51") (name "TRANSFEROUT3") (class "Default")
      (node (ref "IC10") (pin "12") (pinfunction "I0_12") (pintype "input"))
      (node (ref "IC11") (pin "9") (pinfunction "3Y_9") (pintype "output"))
    )
    (net (code "52") (name "TRANSFER_PULSES") (class "Default")
      (node (ref "IC3") (pin "12") (pinfunction "I0_12") (pintype "input"))
      (node (ref "IC3") (pin "9") (pinfunction "I0_9") (pintype "input"))
      (node (ref "IC4") (pin "12") (pinfunction "I0_12") (pintype "input"))
      (node (ref "IC4") (pin "9") (pinfunction "I0_9") (pintype "input"))
      (node (ref "IC7") (pin "12") (pinfunction "I0_12") (pintype "input"))
      (node (ref "IC7") (pin "9") (pinfunction "I0_9") (pintype "input"))
      (node (ref "IC8") (pin "12") (pinfunction "I0_12") (pintype "input"))
      (node (ref "IC8") (pin "9") (pinfunction "I0_9") (pintype "input"))
      (node (ref "JP3") (pin "8") (pinfunction "8_8") (pintype "passive"))
    )
    (net (code "53") (name "VCC") (class "Default")
      (node (ref "C1") (pin "1") (pinfunction "1_1") (pintype "passive"))
      (node (ref "C10") (pin "1") (pinfunction "1_1") (pintype "passive"))
      (node (ref "C11") (pin "1") (pinfunction "1_1") (pintype "passive"))
      (node (ref "C12") (pin "1") (pinfunction "1_1") (pintype "passive"))
      (node (ref "C13") (pin "+") (pinfunction "+_+") (pintype "passive"))
      (node (ref "C14") (pin "+") (pinfunction "+_+") (pintype "passive"))
      (node (ref "C15") (pin "+") (pinfunction "+_+") (pintype "passive"))
      (node (ref "C2") (pin "1") (pinfunction "1_1") (pintype "passive"))
      (node (ref "C3") (pin "1") (pinfunction "1_1") (pintype "passive"))
      (node (ref "C4") (pin "1") (pinfunction "1_1") (pintype "passive"))
      (node (ref "C5") (pin "1") (pinfunction "1_1") (pintype "passive"))
      (node (ref "C6") (pin "1") (pinfunction "1_1") (pintype "passive"))
      (node (ref "C7") (pin "1") (pinfunction "1_1") (pintype "passive"))
      (node (ref "C8") (pin "1") (pinfunction "1_1") (pintype "passive"))
      (node (ref "C9") (pin "1") (pinfunction "1_1") (pintype "passive"))
      (node (ref "IC1") (pin "14") (pinfunction "J_14") (pintype "input"))
      (node (ref "IC1") (pin "4") (pinfunction "VCC_4") (pintype "power_in"))
      (node (ref "IC1") (pin "7") (pinfunction "J_7") (pintype "input"))
      (node (ref "IC10") (pin "14") (pinfunction "VCC_14") (pintype "power_in"))
      (node (ref "IC11") (pin "16") (pinfunction "VCC_16") (pintype "power_in"))
      (node (ref "IC12") (pin "14") (pinfunction "VCC_14") (pintype "power_in"))
      (node (ref "IC2") (pin "14") (pinfunction "J_14") (pintype "input"))
      (node (ref "IC2") (pin "4") (pinfunction "VCC_4") (pintype "power_in"))
      (node (ref "IC2") (pin "7") (pinfunction "J_7") (pintype "input"))
      (node (ref "IC3") (pin "14") (pinfunction "VCC_14") (pintype "power_in"))
      (node (ref "IC4") (pin "14") (pinfunction "VCC_14") (pintype "power_in"))
      (node (ref "IC5") (pin "14") (pinfunction "J_14") (pintype "input"))
      (node (ref "IC5") (pin "4") (pinfunction "VCC_4") (pintype "power_in"))
      (node (ref "IC5") (pin "7") (pinfunction "J_7") (pintype "input"))
      (node (ref "IC6") (pin "14") (pinfunction "J_14") (pintype "input"))
      (node (ref "IC6") (pin "4") (pinfunction "VCC_4") (pintype "power_in"))
      (node (ref "IC6") (pin "7") (pinfunction "J_7") (pintype "input"))
      (node (ref "IC7") (pin "14") (pinfunction "VCC_14") (pintype "power_in"))
      (node (ref "IC8") (pin "14") (pinfunction "VCC_14") (pintype "power_in"))
      (node (ref "IC9") (pin "16") (pinfunction "VCC_16") (pintype "power_in"))
      (node (ref "JP1") (pin "1") (pinfunction "1_1") (pintype "passive"))
      (node (ref "JP1") (pin "2") (pinfunction "2_2") (pintype "passive"))
      (node (ref "JP2") (pin "1") (pinfunction "1_1") (pintype "passive"))
      (node (ref "JP2") (pin "2") (pinfunction "2_2") (pintype "passive"))
      (node (ref "JP3") (pin "1") (pinfunction "1_1") (pintype "passive"))
      (node (ref "JP3") (pin "2") (pinfunction "2_2") (pintype "passive"))
    )
    (net (code "54") (name "ZCR0") (class "Default")
      (node (ref "IC2") (pin "5") (pinfunction "CLK_5") (pintype "input"))
      (node (ref "JP2") (pin "18") (pinfunction "18_18") (pintype "passive"))
    )
    (net (code "55") (name "ZCR1") (class "Default")
      (node (ref "IC2") (pin "1") (pinfunction "CLK_1") (pintype "input"))
      (node (ref "JP2") (pin "14") (pinfunction "14_14") (pintype "passive"))
    )
    (net (code "56") (name "ZCR2") (class "Default")
      (node (ref "IC6") (pin "5") (pinfunction "CLK_5") (pintype "input"))
      (node (ref "JP2") (pin "10") (pinfunction "10_10") (pintype "passive"))
    )
    (net (code "57") (name "ZCR3") (class "Default")
      (node (ref "IC6") (pin "1") (pinfunction "CLK_1") (pintype "input"))
      (node (ref "JP2") (pin "6") (pinfunction "6_6") (pintype "passive"))
    )
    (net (code "58") (name "ZCS0") (class "Default")
      (node (ref "IC1") (pin "1") (pinfunction "CLK_1") (pintype "input"))
      (node (ref "JP1") (pin "18") (pinfunction "18_18") (pintype "passive"))
    )
    (net (code "59") (name "ZCS1") (class "Default")
      (node (ref "IC1") (pin "5") (pinfunction "CLK_5") (pintype "input"))
      (node (ref "JP1") (pin "14") (pinfunction "14_14") (pintype "passive"))
    )
    (net (code "60") (name "ZCS2") (class "Default")
      (node (ref "IC5") (pin "1") (pinfunction "CLK_1") (pintype "input"))
      (node (ref "JP1") (pin "10") (pinfunction "10_10") (pintype "passive"))
    )
    (net (code "61") (name "ZCS3") (class "Default")
      (node (ref "IC5") (pin "5") (pinfunction "CLK_5") (pintype "input"))
      (node (ref "JP1") (pin "6") (pinfunction "6_6") (pintype "passive"))
    )
    (net (code "62") (name "unconnected-(IC9A-G-Pad15)") (class "Default")
      (node (ref "IC9") (pin "15") (pinfunction "G_15") (pintype "input"))
    )
    (net (code "63") (name "unconnected-(IC9A-~{A}{slash}B-Pad1)") (class "Default")
      (node (ref "IC9") (pin "1") (pinfunction "~{A}/B_1") (pintype "input"))
    )
    (net (code "64") (name "unconnected-(IC11A-G-Pad15)") (class "Default")
      (node (ref "IC11") (pin "15") (pinfunction "G_15") (pintype "input"))
    )
    (net (code "65") (name "unconnected-(IC11A-~{A}{slash}B-Pad1)") (class "Default")
      (node (ref "IC11") (pin "1") (pinfunction "~{A}/B_1") (pintype "input"))
    )
    (net (code "66") (name "unconnected-(JP1-Pad3)") (class "Default")
      (node (ref "JP1") (pin "3") (pinfunction "3_3") (pintype "passive"))
    )
    (net (code "67") (name "unconnected-(JP1-Pad4)") (class "Default")
      (node (ref "JP1") (pin "4") (pinfunction "4_4") (pintype "passive"))
    )
    (net (code "68") (name "unconnected-(JP1-Pad7)") (class "Default")
      (node (ref "JP1") (pin "7") (pinfunction "7_7") (pintype "passive"))
    )
    (net (code "69") (name "unconnected-(JP1-Pad8)") (class "Default")
      (node (ref "JP1") (pin "8") (pinfunction "8_8") (pintype "passive"))
    )
    (net (code "70") (name "unconnected-(JP1-Pad11)") (class "Default")
      (node (ref "JP1") (pin "11") (pinfunction "11_11") (pintype "passive"))
    )
    (net (code "71") (name "unconnected-(JP1-Pad12)") (class "Default")
      (node (ref "JP1") (pin "12") (pinfunction "12_12") (pintype "passive"))
    )
    (net (code "72") (name "unconnected-(JP1-Pad15)") (class "Default")
      (node (ref "JP1") (pin "15") (pinfunction "15_15") (pintype "passive"))
    )
    (net (code "73") (name "unconnected-(JP1-Pad16)") (class "Default")
      (node (ref "JP1") (pin "16") (pinfunction "16_16") (pintype "passive"))
    )
    (net (code "74") (name "unconnected-(JP2-Pad3)") (class "Default")
      (node (ref "JP2") (pin "3") (pinfunction "3_3") (pintype "passive"))
    )
    (net (code "75") (name "unconnected-(JP2-Pad4)") (class "Default")
      (node (ref "JP2") (pin "4") (pinfunction "4_4") (pintype "passive"))
    )
    (net (code "76") (name "unconnected-(JP2-Pad7)") (class "Default")
      (node (ref "JP2") (pin "7") (pinfunction "7_7") (pintype "passive"))
    )
    (net (code "77") (name "unconnected-(JP2-Pad8)") (class "Default")
      (node (ref "JP2") (pin "8") (pinfunction "8_8") (pintype "passive"))
    )
    (net (code "78") (name "unconnected-(JP2-Pad11)") (class "Default")
      (node (ref "JP2") (pin "11") (pinfunction "11_11") (pintype "passive"))
    )
    (net (code "79") (name "unconnected-(JP2-Pad12)") (class "Default")
      (node (ref "JP2") (pin "12") (pinfunction "12_12") (pintype "passive"))
    )
    (net (code "80") (name "unconnected-(JP2-Pad15)") (class "Default")
      (node (ref "JP2") (pin "15") (pinfunction "15_15") (pintype "passive"))
    )
    (net (code "81") (name "unconnected-(JP2-Pad16)") (class "Default")
      (node (ref "JP2") (pin "16") (pinfunction "16_16") (pintype "passive"))
    )
    (net (code "82") (name "unconnected-(JP3-Pad5)") (class "Default")
      (node (ref "JP3") (pin "5") (pinfunction "5_5") (pintype "passive"))
    )
    (net (code "83") (name "unconnected-(JP3-Pad6)") (class "Default")
      (node (ref "JP3") (pin "6") (pinfunction "6_6") (pintype "passive"))
    )
    (net (code "84") (name "unconnected-(JP3-Pad7)") (class "Default")
      (node (ref "JP3") (pin "7") (pinfunction "7_7") (pintype "passive"))
    )
    (net (code "85") (name "unconnected-(JP3-Pad9)") (class "Default")
      (node (ref "JP3") (pin "9") (pinfunction "9_9") (pintype "passive"))
    )
    (net (code "86") (name "unconnected-(JP3-Pad10)") (class "Default")
      (node (ref "JP3") (pin "10") (pinfunction "10_10") (pintype "passive"))
    )
    (net (code "87") (name "unconnected-(JP3-Pad11)") (class "Default")
      (node (ref "JP3") (pin "11") (pinfunction "11_11") (pintype "passive"))
    )
    (net (code "88") (name "unconnected-(JP3-Pad13)") (class "Default")
      (node (ref "JP3") (pin "13") (pinfunction "13_13") (pintype "passive"))
    )
    (net (code "89") (name "unconnected-(JP3-Pad14)") (class "Default")
      (node (ref "JP3") (pin "14") (pinfunction "14_14") (pintype "passive"))
    )
    (net (code "90") (name "unconnected-(JP3-Pad15)") (class "Default")
      (node (ref "JP3") (pin "15") (pinfunction "15_15") (pintype "passive"))
    )
    (net (code "91") (name "unconnected-(JP3-Pad17)") (class "Default")
      (node (ref "JP3") (pin "17") (pinfunction "17_17") (pintype "passive"))
    )
    (net (code "92") (name "unconnected-(JP3-Pad18)") (class "Default")
      (node (ref "JP3") (pin "18") (pinfunction "18_18") (pintype "passive"))
    )
  )
)
